# pixracer_fmu.net
KiCad netlist of a schematic drawn in Altium Designer
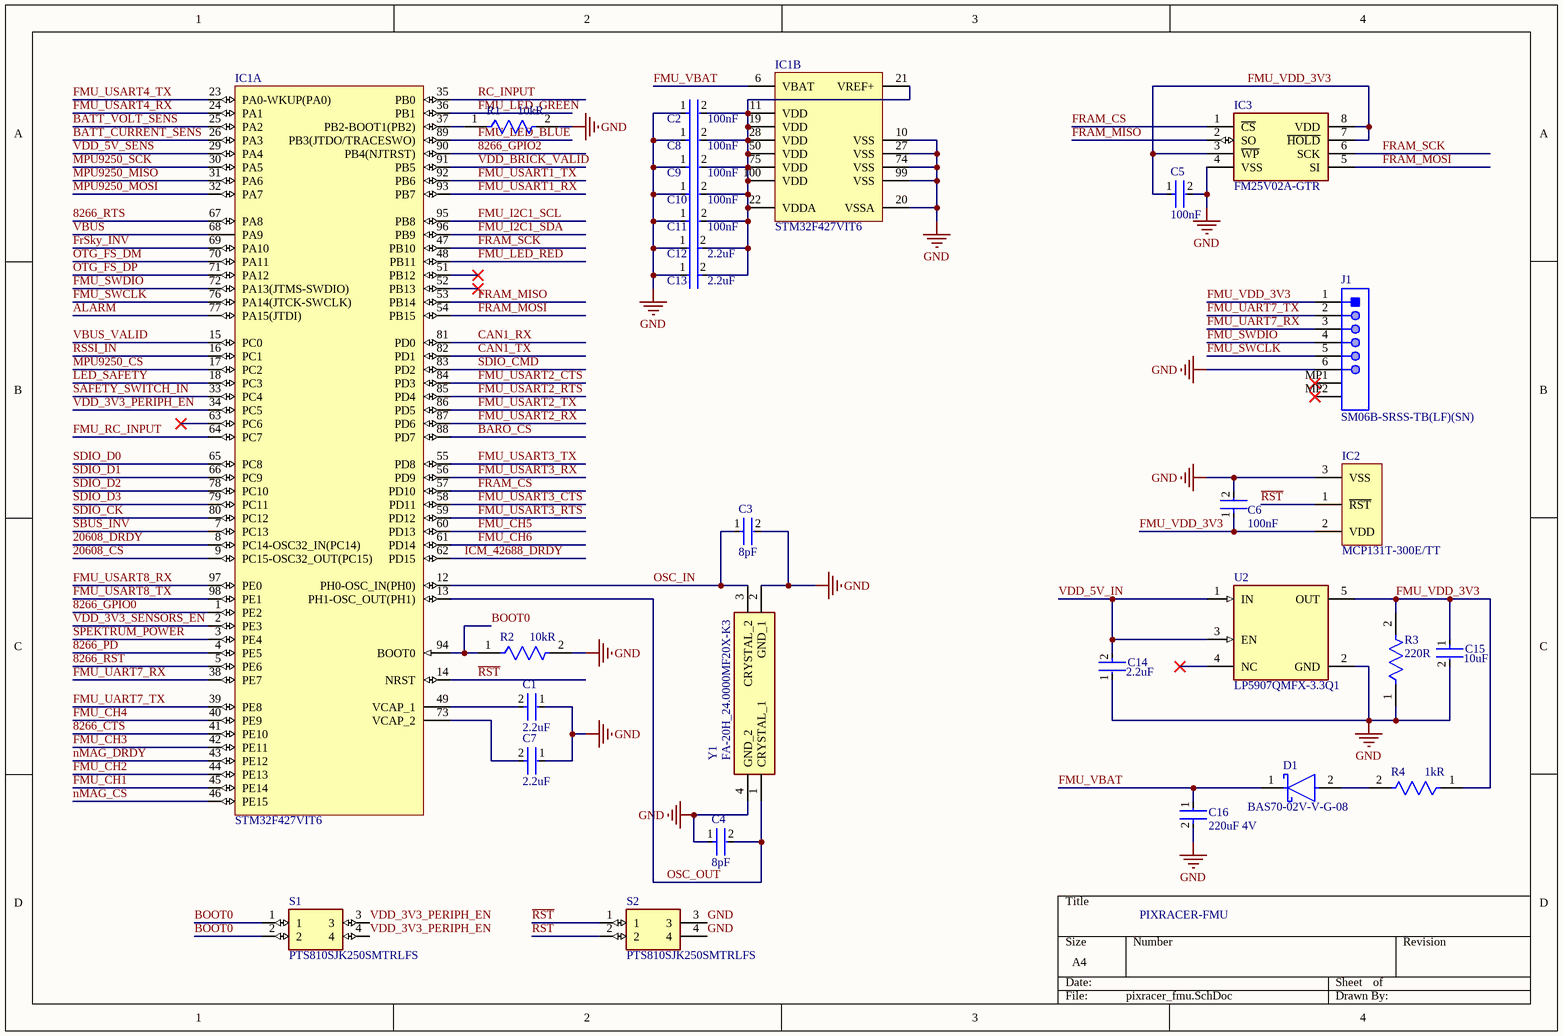
[diagram p0: pixracer_fmu.SchDoc]

(export (version "E")
  (design (tool "Eeschema 10.0.6"))
  (components
    (comp (ref "C1")
      (value "C1608X7R1A225K080AC")
      (footprint "FP-C1608-080-0_1-MFG")
      (description "Multilayer Ceramic Capacitors 2.2μF ±10% 10V X7R SMD 0603")
      (fields (field (name "CAPACITANCE") "2.2uF") (field (name "TOLERANCE") "10%"))
      (libsource (lib "Altium Content Vault") (part "236180d848d6139a670b325ea6854c9"))
    )
    (comp (ref "C2")
      (value "0603ZC104MAT2A")
      (footprint "FP-0603-L_1_6_0_15-W_0_81-IPC_B")
      (description "General Purpose Ceramic Capacitor, 0603, 100nF, 20%, X7R, 15%, 10V")
      (fields (field (name "TOLERANCE") "20%") (field (name "CAPACITANCE") "100nF"))
      (libsource (lib "Altium Content Vault") (part "02cd4be3c70576c341d710602a673aa"))
    )
    (comp (ref "C3")
      (value "CGA3E2C0G1H080D080AA")
      (footprint "FP-CGA3E-0_3-0_1-IPC_A")
      (description "Cap Ceramic 8pF 50V C0G 0.5pF Pad SMD 0603 +125°C Automotive T/R")
      (fields (field (name "CAPACITANCE") "8pF"))
      (libsource (lib "Altium Content Vault") (part "b4654b650e69147ec39a6b967a45e02"))
    )
    (comp (ref "C4")
      (value "CGA3E2C0G1H080D080AA")
      (footprint "FP-CGA3E-0_3-0_1-IPC_A")
      (description "Cap Ceramic 8pF 50V C0G 0.5pF Pad SMD 0603 +125°C Automotive T/R")
      (fields (field (name "CAPACITANCE") "8pF"))
      (libsource (lib "Altium Content Vault") (part "b4654b650e69147ec39a6b967a45e02"))
    )
    (comp (ref "C5")
      (value "0603ZC104MAT2A")
      (footprint "FP-0603-L_1_6_0_15-W_0_81-IPC_B")
      (description "General Purpose Ceramic Capacitor, 0603, 100nF, 20%, X7R, 15%, 10V")
      (fields (field (name "TOLERANCE") "20%") (field (name "CAPACITANCE") "100nF"))
      (libsource (lib "Altium Content Vault") (part "02cd4be3c70576c341d710602a673aa"))
    )
    (comp (ref "C6")
      (value "0603ZC104MAT2A")
      (footprint "FP-0603-L_1_6_0_15-W_0_81-IPC_B")
      (description "General Purpose Ceramic Capacitor, 0603, 100nF, 20%, X7R, 15%, 10V")
      (fields (field (name "TOLERANCE") "20%") (field (name "CAPACITANCE") "100nF"))
      (libsource (lib "Altium Content Vault") (part "02cd4be3c70576c341d710602a673aa"))
    )
    (comp (ref "C7")
      (value "C1608X7R1A225K080AC")
      (footprint "FP-C1608-080-0_1-MFG")
      (description "Multilayer Ceramic Capacitors 2.2μF ±10% 10V X7R SMD 0603")
      (fields (field (name "CAPACITANCE") "2.2uF") (field (name "TOLERANCE") "10%"))
      (libsource (lib "Altium Content Vault") (part "236180d848d6139a670b325ea6854c9"))
    )
    (comp (ref "C8")
      (value "0603ZC104MAT2A")
      (footprint "FP-0603-L_1_6_0_15-W_0_81-IPC_B")
      (description "General Purpose Ceramic Capacitor, 0603, 100nF, 20%, X7R, 15%, 10V")
      (fields (field (name "TOLERANCE") "20%") (field (name "CAPACITANCE") "100nF"))
      (libsource (lib "Altium Content Vault") (part "02cd4be3c70576c341d710602a673aa"))
    )
    (comp (ref "C9")
      (value "0603ZC104MAT2A")
      (footprint "FP-0603-L_1_6_0_15-W_0_81-IPC_B")
      (description "General Purpose Ceramic Capacitor, 0603, 100nF, 20%, X7R, 15%, 10V")
      (fields (field (name "TOLERANCE") "20%") (field (name "CAPACITANCE") "100nF"))
      (libsource (lib "Altium Content Vault") (part "02cd4be3c70576c341d710602a673aa"))
    )
    (comp (ref "C10")
      (value "0603ZC104MAT2A")
      (footprint "FP-0603-L_1_6_0_15-W_0_81-IPC_B")
      (description "General Purpose Ceramic Capacitor, 0603, 100nF, 20%, X7R, 15%, 10V")
      (fields (field (name "TOLERANCE") "20%") (field (name "CAPACITANCE") "100nF"))
      (libsource (lib "Altium Content Vault") (part "02cd4be3c70576c341d710602a673aa"))
    )
    (comp (ref "C11")
      (value "0603ZC104MAT2A")
      (footprint "FP-0603-L_1_6_0_15-W_0_81-IPC_B")
      (description "General Purpose Ceramic Capacitor, 0603, 100nF, 20%, X7R, 15%, 10V")
      (fields (field (name "TOLERANCE") "20%") (field (name "CAPACITANCE") "100nF"))
      (libsource (lib "Altium Content Vault") (part "02cd4be3c70576c341d710602a673aa"))
    )
    (comp (ref "C12")
      (value "C1608X7R1A225K080AC")
      (footprint "FP-C1608-080-0_1-MFG")
      (description "Multilayer Ceramic Capacitors 2.2μF ±10% 10V X7R SMD 0603")
      (fields (field (name "CAPACITANCE") "2.2uF") (field (name "TOLERANCE") "10%"))
      (libsource (lib "Altium Content Vault") (part "236180d848d6139a670b325ea6854c9"))
    )
    (comp (ref "C13")
      (value "C1608X7R1A225K080AC")
      (footprint "FP-C1608-080-0_1-MFG")
      (description "Multilayer Ceramic Capacitors 2.2μF ±10% 10V X7R SMD 0603")
      (fields (field (name "CAPACITANCE") "2.2uF") (field (name "TOLERANCE") "10%"))
      (libsource (lib "Altium Content Vault") (part "236180d848d6139a670b325ea6854c9"))
    )
    (comp (ref "C14")
      (value "C1608X7R1A225K080AC")
      (footprint "FP-C1608-080-0_1-MFG")
      (description "Multilayer Ceramic Capacitors 2.2μF ±10% 10V X7R SMD 0603")
      (fields (field (name "CAPACITANCE") "2.2uF") (field (name "TOLERANCE") "10%"))
      (libsource (lib "Altium Content Vault") (part "236180d848d6139a670b325ea6854c9"))
    )
    (comp (ref "C15")
      (value "CL10A106KP8NNND")
      (footprint "FP-CL10-IPC_B")
      (description "Cap Ceramic 10uF 10V X5R ±10% Pad SMD 0603 +85°C T/R")
      (fields (field (name "TOLERANCE") "10%") (field (name "CAPACITANCE") "10uF"))
      (libsource (lib "Altium Content Vault") (part "b4654b650e69147ec39a6b967a45e02"))
    )
    (comp (ref "C16")
      (value "GRM31CR60G227ME11L")
      (footprint "FP-GRM31C-0_3-e0_3_0_9-IPC_C")
      (description "Chip Multilayer Ceramic Capacitors for General Purpose, 1206, 220uF, X5R, 15%, 20%, 4V")
      (fields (field (name "CAPACITANCE") "220uF 4V") (field (name "TOLERANCE") "20%"))
      (libsource (lib "Altium Content Vault") (part "f23184f103b6ebe33a8c269c53dcba6"))
    )
    (comp (ref "D1")
      (value "BAS70-02V-V-G-08")
      (footprint "FP-S8-V-3880_02-001-MFG")
      (description "DIODE SCHOTTKY 70V 100MA SOD523")
      (fields
        (field (name "OCTOPART") "https://octopart.com/bas70-02v-v-g-08-vishay-44351226")
        (field (name "MANUFACTURER") "Vishay")
      )
      (libsource (lib "Altium Content Vault") (part "1d6ec82d83fb6aee721767c19dac4b9"))
    )
    (comp (ref "IC1")
      (value "STM32F427VIT6")
      (footprint "STM-LQFP100_N")
      (fields (field (name "MANUFACTURER") "STMicroelectronics"))
      (libsource (lib "Altium Content Vault") (part "MC-ARM-STM32F4X7-SQ100"))
    )
    (comp (ref "IC2")
      (value "MCP131T-300E/TT")
      (footprint "SOT-23-TT3_N")
      (description "Micropower Voltage Supervisors, 3-Pin SOT-23, Extended Temperature, Tape and Reel")
      (libsource (lib "Altium Content Vault") (part "PM-SCCT-MCP121-3"))
    )
    (comp (ref "IC3")
      (value "FM25V02A-GTR")
      (footprint "SamacSys:SOIC127P602X173-8N")
      (description "Integrated Circuit")
      (fields (field (name "MOUSER PART NUMBER") "727-FM25V02A-GTR"))
      (libsource (lib "*") (part "FM25V02A-GTR"))
    )
    (comp (ref "J1")
      (value "SM06B-SRSS-TB(LF)(SN)")
      (footprint "JST-SM06B-SRSS-TB_V")
      (description "Male Header, Pitch 1 mm, 1 x 6 Position, Height 2.95 mm, -25 to 85 degC, RoHS, Tape and Reel")
      (fields (field (name "MANUFACTURER") "JST"))
      (libsource (lib "Altium Content Vault") (part "CN-1P-2M-R6"))
    )
    (comp (ref "R1")
      (value "ERJ-3GEYJ103V")
      (footprint "FP-ERJ3G-IPC_C")
      (description "RES SMD 10K OHM 5% 1/10W 0603")
      (fields (field (name "TOLERANCE") "5%") (field (name "RESISTANCE") "10kR"))
      (libsource (lib "Altium Content Vault") (part "1029c3af85768c4190bb7ad29bc67b5"))
    )
    (comp (ref "R2")
      (value "ERJ-3GEYJ103V")
      (footprint "FP-ERJ3G-IPC_C")
      (description "RES SMD 10K OHM 5% 1/10W 0603")
      (fields (field (name "TOLERANCE") "5%") (field (name "RESISTANCE") "10kR"))
      (libsource (lib "Altium Content Vault") (part "1029c3af85768c4190bb7ad29bc67b5"))
    )
    (comp (ref "R3")
      (value "CRCW0603220RFKEB")
      (footprint "FP-CRCW0603-e3-MFG")
      (description "RES Thick Film, 220Ω, 1%, 0.1W, 100ppm/°C, 0603")
      (fields (field (name "TOLERANCE") "1%") (field (name "RESISTANCE") "220R"))
      (libsource (lib "Altium Content Vault") (part "1029c3af85768c4190bb7ad29bc67b5"))
    )
    (comp (ref "R4")
      (value "RC1608J102CS")
      (footprint "FP-RC1608-IPC_A")
      (description "Res Thick Film 0603 1kΩ 5% 0.1W ±100ppm/°C Molded SMD T/R")
      (fields (field (name "RESISTANCE") "1kR") (field (name "TOLERANCE") "5%"))
      (libsource (lib "Altium Content Vault") (part "1029c3af85768c4190bb7ad29bc67b5"))
    )
    (comp (ref "S1")
      (value "PTS810SJK250SMTRLFS")
      (footprint "PTS810SJG250SMTRLFS")
      (description "Tactile Switch SPST-NO Top Actuated Surface Mount")
      (fields (field (name "MF") "C&K") (field (name "MP") "PTS810 SJK 250 SMTR LFS"))
      (libsource (lib "PTS810SJK250SMTRLFS") (part "PTS810SJK250SMTRLFS"))
    )
    (comp (ref "S2")
      (value "PTS810SJK250SMTRLFS")
      (footprint "PTS810SJG250SMTRLFS")
      (description "Tactile Switch SPST-NO Top Actuated Surface Mount")
      (fields (field (name "MF") "C&K") (field (name "MP") "PTS810 SJK 250 SMTR LFS"))
      (libsource (lib "PTS810SJK250SMTRLFS") (part "PTS810SJK250SMTRLFS"))
    )
    (comp (ref "U2")
      (value "LP5907QMFX-3.3Q1")
      (footprint "FP-DBV0005A-MFG")
      (description "IC REG LINEAR 3.3V 250MA SOT23-5")
      (fields
        (field (name "MANUFACTURER") "Texas Instruments")
        (field (name "OCTOPART") "https://octopart.com/lp5907qmfx-3.3q1-texas+instruments-50417899")
      )
      (libsource (lib "Altium Content Vault") (part "e6eddeb8bab6a4ee265087e5808ab9f"))
    )
    (comp (ref "Y1")
      (value "FA-20H_24.0000MF20X-K3")
      (footprint "SamacSys:FA20H160000MF12ZAC3")
      (description "Crystal or Oscillator")
      (fields
        (field (name "MANUFACTURER_PART_NUMBER") "FA-20H 24.0000MF20X-K3")
        (field (name "MOUSER PART NUMBER") "732-FA20H-24F20X-K3")
      )
      (libsource (lib "*") (part "FA-20H_24.0000MF20X-K3"))
    )
  )
  (nets
    (net (code "1") (name "/8266_CTS") (class "Default")
      (node (ref "IC1") (pin "41") (pinfunction "PE10_41") (pintype "bidirectional"))
    )
    (net (code "2") (name "/8266_GPIO0") (class "Default")
      (node (ref "IC1") (pin "1") (pinfunction "PE2_1") (pintype "bidirectional"))
    )
    (net (code "3") (name "/8266_GPIO2") (class "Default")
      (node (ref "IC1") (pin "90") (pinfunction "PB4(NJTRST)_90") (pintype "bidirectional"))
    )
    (net (code "4") (name "/8266_PD") (class "Default")
      (node (ref "IC1") (pin "4") (pinfunction "PE5_4") (pintype "bidirectional"))
    )
    (net (code "5") (name "/8266_RST") (class "Default")
      (node (ref "IC1") (pin "5") (pinfunction "PE6_5") (pintype "bidirectional"))
    )
    (net (code "6") (name "/8266_RTS") (class "Default")
      (node (ref "IC1") (pin "67") (pinfunction "PA8_67") (pintype "bidirectional"))
    )
    (net (code "7") (name "/20608_CS") (class "Default")
      (node (ref "IC1") (pin "9") (pinfunction "PC15-OSC32_OUT(PC15)_9") (pintype "bidirectional"))
    )
    (net (code "8") (name "/20608_DRDY") (class "Default")
      (node (ref "IC1") (pin "8") (pinfunction "PC14-OSC32_IN(PC14)_8") (pintype "bidirectional"))
    )
    (net (code "9") (name "/ALARM") (class "Default")
      (node (ref "IC1") (pin "77") (pinfunction "PA15(JTDI)_77") (pintype "bidirectional"))
    )
    (net (code "10") (name "/BARO_CS") (class "Default")
      (node (ref "IC1") (pin "88") (pinfunction "PD7_88") (pintype "bidirectional"))
    )
    (net (code "11") (name "/BATT_CURRENT_SENS") (class "Default")
      (node (ref "IC1") (pin "26") (pinfunction "PA3_26") (pintype "bidirectional"))
    )
    (net (code "12") (name "/BATT_VOLT_SENS") (class "Default")
      (node (ref "IC1") (pin "25") (pinfunction "PA2_25") (pintype "bidirectional"))
    )
    (net (code "13") (name "/BOOT0") (class "Default")
      (node (ref "IC1") (pin "94") (pinfunction "BOOT0_94") (pintype "input"))
      (node (ref "R2") (pin "1") (pinfunction "1_1") (pintype "passive"))
      (node (ref "S1") (pin "1") (pinfunction "1_1") (pintype "bidirectional"))
      (node (ref "S1") (pin "2") (pinfunction "2_2") (pintype "bidirectional"))
    )
    (net (code "14") (name "/CAN1_RX") (class "Default")
      (node (ref "IC1") (pin "81") (pinfunction "PD0_81") (pintype "bidirectional"))
    )
    (net (code "15") (name "/CAN1_TX") (class "Default")
      (node (ref "IC1") (pin "82") (pinfunction "PD1_82") (pintype "bidirectional"))
    )
    (net (code "16") (name "/FMU_CH1") (class "Default")
      (node (ref "IC1") (pin "45") (pinfunction "PE14_45") (pintype "bidirectional"))
    )
    (net (code "17") (name "/FMU_CH2") (class "Default")
      (node (ref "IC1") (pin "44") (pinfunction "PE13_44") (pintype "bidirectional"))
    )
    (net (code "18") (name "/FMU_CH3") (class "Default")
      (node (ref "IC1") (pin "42") (pinfunction "PE11_42") (pintype "bidirectional"))
    )
    (net (code "19") (name "/FMU_CH4") (class "Default")
      (node (ref "IC1") (pin "40") (pinfunction "PE9_40") (pintype "bidirectional"))
    )
    (net (code "20") (name "/FMU_CH5") (class "Default")
      (node (ref "IC1") (pin "60") (pinfunction "PD13_60") (pintype "bidirectional"))
    )
    (net (code "21") (name "/FMU_CH6") (class "Default")
      (node (ref "IC1") (pin "61") (pinfunction "PD14_61") (pintype "bidirectional"))
    )
    (net (code "22") (name "/FMU_I2C1_SCL") (class "Default")
      (node (ref "IC1") (pin "95") (pinfunction "PB8_95") (pintype "bidirectional"))
    )
    (net (code "23") (name "/FMU_I2C1_SDA") (class "Default")
      (node (ref "IC1") (pin "96") (pinfunction "PB9_96") (pintype "bidirectional"))
    )
    (net (code "24") (name "/FMU_LED_BLUE") (class "Default")
      (node (ref "IC1") (pin "89") (pinfunction "PB3(JTDO/TRACESWO)_89") (pintype "bidirectional"))
    )
    (net (code "25") (name "/FMU_LED_GREEN") (class "Default")
      (node (ref "IC1") (pin "36") (pinfunction "PB1_36") (pintype "bidirectional"))
    )
    (net (code "26") (name "/FMU_LED_RED") (class "Default")
      (node (ref "IC1") (pin "48") (pinfunction "PB11_48") (pintype "bidirectional"))
    )
    (net (code "27") (name "/FMU_RC_INPUT") (class "Default")
      (node (ref "IC1") (pin "64") (pinfunction "PC7_64") (pintype "bidirectional"))
    )
    (net (code "28") (name "/FMU_SWCLK") (class "Default")
      (node (ref "IC1") (pin "76") (pinfunction "PA14(JTCK-SWCLK)_76") (pintype "bidirectional"))
      (node (ref "J1") (pin "5") (pinfunction "5_5") (pintype "passive"))
    )
    (net (code "29") (name "/FMU_SWDIO") (class "Default")
      (node (ref "IC1") (pin "72") (pinfunction "PA13(JTMS-SWDIO)_72") (pintype "bidirectional"))
      (node (ref "J1") (pin "4") (pinfunction "4_4") (pintype "passive"))
    )
    (net (code "30") (name "/FMU_UART7_RX") (class "Default")
      (node (ref "IC1") (pin "38") (pinfunction "PE7_38") (pintype "bidirectional"))
      (node (ref "J1") (pin "3") (pinfunction "3_3") (pintype "passive"))
    )
    (net (code "31") (name "/FMU_UART7_TX") (class "Default")
      (node (ref "IC1") (pin "39") (pinfunction "PE8_39") (pintype "bidirectional"))
      (node (ref "J1") (pin "2") (pinfunction "2_2") (pintype "passive"))
    )
    (net (code "32") (name "/FMU_USART1_RX") (class "Default")
      (node (ref "IC1") (pin "93") (pinfunction "PB7_93") (pintype "bidirectional"))
    )
    (net (code "33") (name "/FMU_USART1_TX") (class "Default")
      (node (ref "IC1") (pin "92") (pinfunction "PB6_92") (pintype "bidirectional"))
    )
    (net (code "34") (name "/FMU_USART2_CTS") (class "Default")
      (node (ref "IC1") (pin "84") (pinfunction "PD3_84") (pintype "bidirectional"))
    )
    (net (code "35") (name "/FMU_USART2_RTS") (class "Default")
      (node (ref "IC1") (pin "85") (pinfunction "PD4_85") (pintype "bidirectional"))
    )
    (net (code "36") (name "/FMU_USART2_RX") (class "Default")
      (node (ref "IC1") (pin "87") (pinfunction "PD6_87") (pintype "bidirectional"))
    )
    (net (code "37") (name "/FMU_USART2_TX") (class "Default")
      (node (ref "IC1") (pin "86") (pinfunction "PD5_86") (pintype "bidirectional"))
    )
    (net (code "38") (name "/FMU_USART3_CTS") (class "Default")
      (node (ref "IC1") (pin "58") (pinfunction "PD11_58") (pintype "bidirectional"))
    )
    (net (code "39") (name "/FMU_USART3_RTS") (class "Default")
      (node (ref "IC1") (pin "59") (pinfunction "PD12_59") (pintype "bidirectional"))
    )
    (net (code "40") (name "/FMU_USART3_RX") (class "Default")
      (node (ref "IC1") (pin "56") (pinfunction "PD9_56") (pintype "bidirectional"))
    )
    (net (code "41") (name "/FMU_USART3_TX") (class "Default")
      (node (ref "IC1") (pin "55") (pinfunction "PD8_55") (pintype "bidirectional"))
    )
    (net (code "42") (name "/FMU_USART4_RX") (class "Default")
      (node (ref "IC1") (pin "24") (pinfunction "PA1_24") (pintype "bidirectional"))
    )
    (net (code "43") (name "/FMU_USART4_TX") (class "Default")
      (node (ref "IC1") (pin "23") (pinfunction "PA0-WKUP(PA0)_23") (pintype "bidirectional"))
    )
    (net (code "44") (name "/FMU_USART8_RX") (class "Default")
      (node (ref "IC1") (pin "97") (pinfunction "PE0_97") (pintype "bidirectional"))
    )
    (net (code "45") (name "/FMU_USART8_TX") (class "Default")
      (node (ref "IC1") (pin "98") (pinfunction "PE1_98") (pintype "bidirectional"))
    )
    (net (code "46") (name "/FMU_VBAT") (class "Default")
      (node (ref "C16") (pin "1") (pinfunction "1_1") (pintype "passive"))
      (node (ref "D1") (pin "1") (pinfunction "C_1") (pintype "passive"))
      (node (ref "IC1") (pin "6") (pinfunction "VBAT_6") (pintype "power_in"))
    )
    (net (code "47") (name "/FMU_VDD_3V3") (class "Default")
      (node (ref "C15") (pin "1") (pinfunction "1_1") (pintype "passive"))
      (node (ref "C5") (pin "1") (pinfunction "1_1") (pintype "passive"))
      (node (ref "C6") (pin "1") (pinfunction "1_1") (pintype "passive"))
      (node (ref "IC2") (pin "2") (pinfunction "VDD_2") (pintype "power_in"))
      (node (ref "IC3") (pin "3") (pinfunction "~{WP}_3") (pintype "passive"))
      (node (ref "IC3") (pin "7") (pinfunction "~{HOLD}_7") (pintype "passive"))
      (node (ref "IC3") (pin "8") (pinfunction "VDD_8") (pintype "passive"))
      (node (ref "J1") (pin "1") (pinfunction "1_1") (pintype "passive"))
      (node (ref "R3") (pin "2") (pinfunction "2_2") (pintype "passive"))
      (node (ref "R4") (pin "1") (pinfunction "1_1") (pintype "passive"))
      (node (ref "U2") (pin "5") (pinfunction "OUT_5") (pintype "power_in"))
    )
    (net (code "48") (name "/FRAM_CS") (class "Default")
      (node (ref "IC1") (pin "57") (pinfunction "PD10_57") (pintype "bidirectional"))
      (node (ref "IC3") (pin "1") (pinfunction "~{CS}_1") (pintype "passive"))
    )
    (net (code "49") (name "/FRAM_MISO") (class "Default")
      (node (ref "IC1") (pin "53") (pinfunction "PB14_53") (pintype "bidirectional"))
      (node (ref "IC3") (pin "2") (pinfunction "SO_2") (pintype "bidirectional"))
    )
    (net (code "50") (name "/FRAM_MOSI") (class "Default")
      (node (ref "IC1") (pin "54") (pinfunction "PB15_54") (pintype "bidirectional"))
      (node (ref "IC3") (pin "5") (pinfunction "SI_5") (pintype "passive"))
    )
    (net (code "51") (name "/FRAM_SCK") (class "Default")
      (node (ref "IC1") (pin "47") (pinfunction "PB10_47") (pintype "bidirectional"))
      (node (ref "IC3") (pin "6") (pinfunction "SCK_6") (pintype "passive"))
    )
    (net (code "52") (name "/FrSky_INV") (class "Default")
      (node (ref "IC1") (pin "69") (pinfunction "PA10_69") (pintype "bidirectional"))
    )
    (net (code "53") (name "/ICM_42688_DRDY") (class "Default")
      (node (ref "IC1") (pin "62") (pinfunction "PD15_62") (pintype "bidirectional"))
    )
    (net (code "54") (name "/LED_SAFETY") (class "Default")
      (node (ref "IC1") (pin "18") (pinfunction "PC3_18") (pintype "bidirectional"))
    )
    (net (code "55") (name "/MPU9250_CS") (class "Default")
      (node (ref "IC1") (pin "17") (pinfunction "PC2_17") (pintype "bidirectional"))
    )
    (net (code "56") (name "/MPU9250_MISO") (class "Default")
      (node (ref "IC1") (pin "31") (pinfunction "PA6_31") (pintype "bidirectional"))
    )
    (net (code "57") (name "/MPU9250_MOSI") (class "Default")
      (node (ref "IC1") (pin "32") (pinfunction "PA7_32") (pintype "bidirectional"))
    )
    (net (code "58") (name "/MPU9250_SCK") (class "Default")
      (node (ref "IC1") (pin "30") (pinfunction "PA5_30") (pintype "bidirectional"))
    )
    (net (code "59") (name "/OSC_IN") (class "Default")
      (node (ref "C3") (pin "1") (pinfunction "1_1") (pintype "passive"))
      (node (ref "IC1") (pin "12") (pinfunction "PH0-OSC_IN(PH0)_12") (pintype "bidirectional"))
      (node (ref "Y1") (pin "3") (pinfunction "CRYSTAL_2_3") (pintype "passive"))
    )
    (net (code "60") (name "/OSC_OUT") (class "Default")
      (node (ref "C4") (pin "2") (pinfunction "2_2") (pintype "passive"))
      (node (ref "IC1") (pin "13") (pinfunction "PH1-OSC_OUT(PH1)_13") (pintype "bidirectional"))
      (node (ref "Y1") (pin "1") (pinfunction "CRYSTAL_1_1") (pintype "passive"))
    )
    (net (code "61") (name "/OTG_FS_DM") (class "Default")
      (node (ref "IC1") (pin "70") (pinfunction "PA11_70") (pintype "bidirectional"))
    )
    (net (code "62") (name "/OTG_FS_DP") (class "Default")
      (node (ref "IC1") (pin "71") (pinfunction "PA12_71") (pintype "bidirectional"))
    )
    (net (code "63") (name "/RC_INPUT") (class "Default")
      (node (ref "IC1") (pin "35") (pinfunction "PB0_35") (pintype "bidirectional"))
    )
    (net (code "64") (name "/RSSI_IN") (class "Default")
      (node (ref "IC1") (pin "16") (pinfunction "PC1_16") (pintype "bidirectional"))
    )
    (net (code "65") (name "/SAFETY_SWITCH_IN") (class "Default")
      (node (ref "IC1") (pin "33") (pinfunction "PC4_33") (pintype "bidirectional"))
    )
    (net (code "66") (name "/SBUS_INV") (class "Default")
      (node (ref "IC1") (pin "7") (pinfunction "PC13_7") (pintype "bidirectional"))
    )
    (net (code "67") (name "/SDIO_CK") (class "Default")
      (node (ref "IC1") (pin "80") (pinfunction "PC12_80") (pintype "bidirectional"))
    )
    (net (code "68") (name "/SDIO_CMD") (class "Default")
      (node (ref "IC1") (pin "83") (pinfunction "PD2_83") (pintype "bidirectional"))
    )
    (net (code "69") (name "/SDIO_D0") (class "Default")
      (node (ref "IC1") (pin "65") (pinfunction "PC8_65") (pintype "bidirectional"))
    )
    (net (code "70") (name "/SDIO_D1") (class "Default")
      (node (ref "IC1") (pin "66") (pinfunction "PC9_66") (pintype "bidirectional"))
    )
    (net (code "71") (name "/SDIO_D2") (class "Default")
      (node (ref "IC1") (pin "78") (pinfunction "PC10_78") (pintype "bidirectional"))
    )
    (net (code "72") (name "/SDIO_D3") (class "Default")
      (node (ref "IC1") (pin "79") (pinfunction "PC11_79") (pintype "bidirectional"))
    )
    (net (code "73") (name "/SPEKTRUM_POWER") (class "Default")
      (node (ref "IC1") (pin "3") (pinfunction "PE4_3") (pintype "bidirectional"))
    )
    (net (code "74") (name "/VBUS") (class "Default")
      (node (ref "IC1") (pin "68") (pinfunction "PA9_68") (pintype "bidirectional"))
    )
    (net (code "75") (name "/VBUS_VALID") (class "Default")
      (node (ref "IC1") (pin "15") (pinfunction "PC0_15") (pintype "bidirectional"))
    )
    (net (code "76") (name "/VDD_3V3_PERIPH_EN") (class "Default")
      (node (ref "IC1") (pin "34") (pinfunction "PC5_34") (pintype "bidirectional"))
      (node (ref "S1") (pin "3") (pinfunction "3_3") (pintype "bidirectional"))
      (node (ref "S1") (pin "4") (pinfunction "4_4") (pintype "bidirectional"))
    )
    (net (code "77") (name "/VDD_3V3_SENSORS_EN") (class "Default")
      (node (ref "IC1") (pin "2") (pinfunction "PE3_2") (pintype "bidirectional"))
    )
    (net (code "78") (name "/VDD_5V_IN") (class "Default")
      (node (ref "C14") (pin "2") (pinfunction "2_2") (pintype "passive"))
      (node (ref "U2") (pin "1") (pinfunction "IN_1") (pintype "input"))
      (node (ref "U2") (pin "3") (pinfunction "EN_3") (pintype "input"))
    )
    (net (code "79") (name "/VDD_5V_SENS") (class "Default")
      (node (ref "IC1") (pin "29") (pinfunction "PA4_29") (pintype "bidirectional"))
    )
    (net (code "80") (name "/VDD_BRICK_VALID") (class "Default")
      (node (ref "IC1") (pin "91") (pinfunction "PB5_91") (pintype "bidirectional"))
    )
    (net (code "81") (name "/nMAG_CS") (class "Default")
      (node (ref "IC1") (pin "46") (pinfunction "PE15_46") (pintype "bidirectional"))
    )
    (net (code "82") (name "/nMAG_DRDY") (class "Default")
      (node (ref "IC1") (pin "43") (pinfunction "PE12_43") (pintype "bidirectional"))
    )
    (net (code "83") (name "/~{RST}") (class "Default")
      (node (ref "IC1") (pin "14") (pinfunction "NRST_14") (pintype "bidirectional"))
      (node (ref "IC2") (pin "1") (pinfunction "~{RST}_1") (pintype "open_collector"))
      (node (ref "S2") (pin "1") (pinfunction "1_1") (pintype "bidirectional"))
      (node (ref "S2") (pin "2") (pinfunction "2_2") (pintype "bidirectional"))
    )
    (net (code "84") (name "GND") (class "Default")
      (node (ref "C1") (pin "1") (pinfunction "1_1") (pintype "passive"))
      (node (ref "C10") (pin "1") (pinfunction "1_1") (pintype "passive"))
      (node (ref "C11") (pin "1") (pinfunction "1_1") (pintype "passive"))
      (node (ref "C12") (pin "1") (pinfunction "1_1") (pintype "passive"))
      (node (ref "C13") (pin "1") (pinfunction "1_1") (pintype "passive"))
      (node (ref "C14") (pin "1") (pinfunction "1_1") (pintype "passive"))
      (node (ref "C15") (pin "2") (pinfunction "2_2") (pintype "passive"))
      (node (ref "C16") (pin "2") (pinfunction "2_2") (pintype "passive"))
      (node (ref "C2") (pin "1") (pinfunction "1_1") (pintype "passive"))
      (node (ref "C3") (pin "2") (pinfunction "2_2") (pintype "passive"))
      (node (ref "C4") (pin "1") (pinfunction "1_1") (pintype "passive"))
      (node (ref "C5") (pin "2") (pinfunction "2_2") (pintype "passive"))
      (node (ref "C6") (pin "2") (pinfunction "2_2") (pintype "passive"))
      (node (ref "C7") (pin "1") (pinfunction "1_1") (pintype "passive"))
      (node (ref "C8") (pin "1") (pinfunction "1_1") (pintype "passive"))
      (node (ref "C9") (pin "1") (pinfunction "1_1") (pintype "passive"))
      (node (ref "IC1") (pin "10") (pinfunction "VSS_10") (pintype "power_in"))
      (node (ref "IC1") (pin "20") (pinfunction "VSSA_20") (pintype "power_in"))
      (node (ref "IC1") (pin "27") (pinfunction "VSS_27") (pintype "power_in"))
      (node (ref "IC1") (pin "74") (pinfunction "VSS_74") (pintype "power_in"))
      (node (ref "IC1") (pin "99") (pinfunction "VSS_99") (pintype "power_in"))
      (node (ref "IC2") (pin "3") (pinfunction "VSS_3") (pintype "power_in"))
      (node (ref "IC3") (pin "4") (pinfunction "VSS_4") (pintype "passive"))
      (node (ref "J1") (pin "6") (pinfunction "6_6") (pintype "passive"))
      (node (ref "R1") (pin "2") (pinfunction "2_2") (pintype "passive"))
      (node (ref "R2") (pin "2") (pinfunction "2_2") (pintype "passive"))
      (node (ref "R3") (pin "1") (pinfunction "1_1") (pintype "passive"))
      (node (ref "S2") (pin "3") (pinfunction "3_3") (pintype "bidirectional"))
      (node (ref "S2") (pin "4") (pinfunction "4_4") (pintype "bidirectional"))
      (node (ref "U2") (pin "2") (pinfunction "GND_2") (pintype "power_in"))
      (node (ref "Y1") (pin "2") (pinfunction "GND_1_2") (pintype "passive"))
      (node (ref "Y1") (pin "4") (pinfunction "GND_2_4") (pintype "passive"))
    )
    (net (code "85") (name "Net-(D1-A)") (class "Default")
      (node (ref "D1") (pin "2") (pinfunction "A_2") (pintype "passive"))
      (node (ref "R4") (pin "2") (pinfunction "2_2") (pintype "passive"))
    )
    (net (code "86") (name "Net-(IC1A-PB2-BOOT1(PB2))") (class "Default")
      (node (ref "IC1") (pin "37") (pinfunction "PB2-BOOT1(PB2)_37") (pintype "bidirectional"))
      (node (ref "R1") (pin "1") (pinfunction "1_1") (pintype "passive"))
    )
    (net (code "87") (name "Net-(IC1A-VCAP_1)") (class "Default")
      (node (ref "C1") (pin "2") (pinfunction "2_2") (pintype "passive"))
      (node (ref "IC1") (pin "49") (pinfunction "VCAP_1_49") (pintype "power_in"))
    )
    (net (code "88") (name "Net-(IC1A-VCAP_2)") (class "Default")
      (node (ref "C7") (pin "2") (pinfunction "2_2") (pintype "passive"))
      (node (ref "IC1") (pin "73") (pinfunction "VCAP_2_73") (pintype "power_in"))
    )
    (net (code "89") (name "Net-(IC1B-VDDA)") (class "Default")
      (node (ref "C10") (pin "2") (pinfunction "2_2") (pintype "passive"))
      (node (ref "C11") (pin "2") (pinfunction "2_2") (pintype "passive"))
      (node (ref "C12") (pin "2") (pinfunction "2_2") (pintype "passive"))
      (node (ref "C13") (pin "2") (pinfunction "2_2") (pintype "passive"))
      (node (ref "C2") (pin "2") (pinfunction "2_2") (pintype "passive"))
      (node (ref "C8") (pin "2") (pinfunction "2_2") (pintype "passive"))
      (node (ref "C9") (pin "2") (pinfunction "2_2") (pintype "passive"))
      (node (ref "IC1") (pin "100") (pinfunction "VDD_100") (pintype "power_in"))
      (node (ref "IC1") (pin "11") (pinfunction "VDD_11") (pintype "power_in"))
      (node (ref "IC1") (pin "19") (pinfunction "VDD_19") (pintype "power_in"))
      (node (ref "IC1") (pin "21") (pinfunction "VREF+_21") (pintype "power_in"))
      (node (ref "IC1") (pin "22") (pinfunction "VDDA_22") (pintype "power_in"))
      (node (ref "IC1") (pin "28") (pinfunction "VDD_28") (pintype "power_in"))
      (node (ref "IC1") (pin "50") (pinfunction "VDD_50") (pintype "power_in"))
      (node (ref "IC1") (pin "75") (pinfunction "VDD_75") (pintype "power_in"))
    )
    (net (code "90") (name "unconnected-(IC1A-PB12-Pad51)") (class "Default")
      (node (ref "IC1") (pin "51") (pinfunction "PB12_51") (pintype "bidirectional+no_connect"))
    )
    (net (code "91") (name "unconnected-(IC1A-PB13-Pad52)") (class "Default")
      (node (ref "IC1") (pin "52") (pinfunction "PB13_52") (pintype "bidirectional+no_connect"))
    )
    (net (code "92") (name "unconnected-(IC1A-PC6-Pad63)") (class "Default")
      (node (ref "IC1") (pin "63") (pinfunction "PC6_63") (pintype "bidirectional+no_connect"))
    )
    (net (code "93") (name "unconnected-(J1-PadMP1)") (class "Default")
      (node (ref "J1") (pin "MP1") (pinfunction "MP1_MP1") (pintype "passive+no_connect"))
    )
    (net (code "94") (name "unconnected-(J1-PadMP2)") (class "Default")
      (node (ref "J1") (pin "MP2") (pinfunction "MP2_MP2") (pintype "passive+no_connect"))
    )
    (net (code "95") (name "unconnected-(U2-NC-Pad4)") (class "Default")
      (node (ref "U2") (pin "4") (pinfunction "NC_4") (pintype "passive+no_connect"))
    )
  )
)
